# USB-TO-UART.net
KiCad netlist of a schematic drawn in Altium Designer
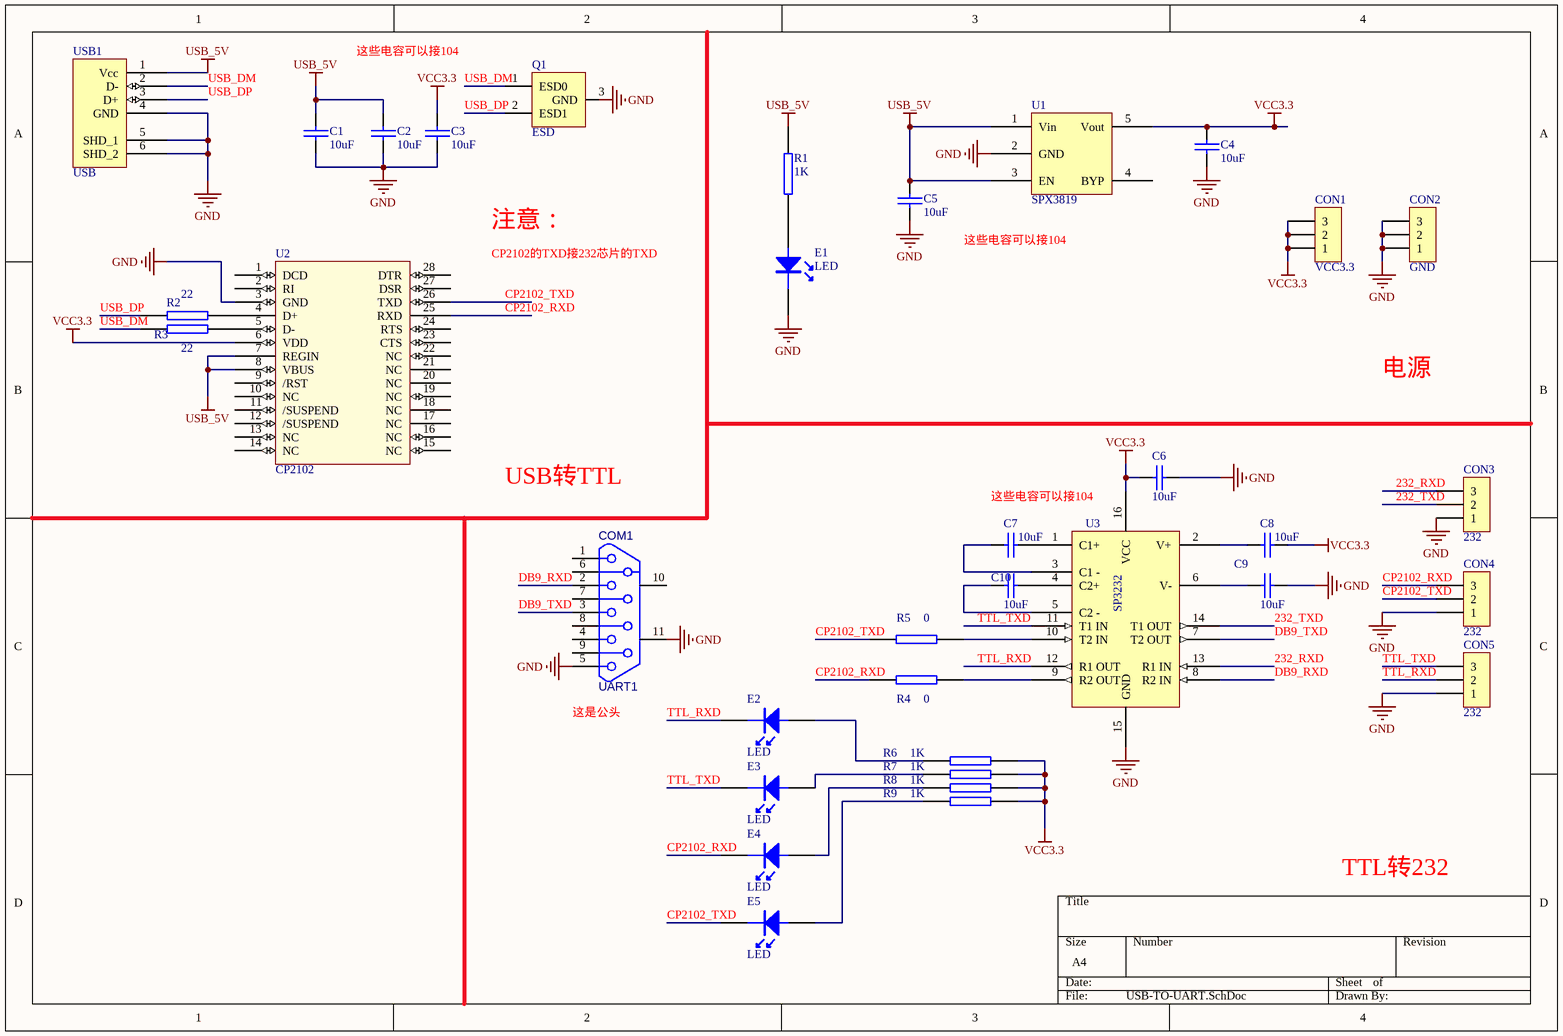
[diagram p0: USB-TO-UART.SchDoc]

(export (version "E")
  (design (tool "Eeschema 10.0.6"))
  (components
    (comp (ref "C1")
      (value "10uF")
      (footprint "0603")
      (description "无极电容")
      (libsource (lib "ZXBC") (part "CAP Nonpolarity"))
    )
    (comp (ref "C2")
      (value "10uF")
      (footprint "0603")
      (description "无极电容")
      (libsource (lib "ZXBC") (part "CAP Nonpolarity"))
    )
    (comp (ref "C3")
      (value "10uF")
      (footprint "0603")
      (description "无极电容")
      (libsource (lib "ZXBC") (part "CAP Nonpolarity"))
    )
    (comp (ref "C4")
      (value "10uF")
      (footprint "0603")
      (description "无极电容")
      (libsource (lib "ZXBC") (part "CAP Nonpolarity"))
    )
    (comp (ref "C5")
      (value "10uF")
      (footprint "0603")
      (description "无极电容")
      (libsource (lib "ZXBC") (part "CAP Nonpolarity"))
    )
    (comp (ref "C6")
      (value "10uF")
      (footprint "0603")
      (description "无极电容")
      (libsource (lib "ZXBC") (part "CAP Nonpolarity"))
    )
    (comp (ref "C7")
      (value "10uF")
      (footprint "0603")
      (description "无极电容")
      (libsource (lib "ZXBC") (part "CAP Nonpolarity"))
    )
    (comp (ref "C8")
      (value "10uF")
      (footprint "0603")
      (description "无极电容")
      (libsource (lib "ZXBC") (part "CAP Nonpolarity"))
    )
    (comp (ref "C9")
      (value "10uF")
      (footprint "0603")
      (description "无极电容")
      (libsource (lib "ZXBC") (part "CAP Nonpolarity"))
    )
    (comp (ref "C10")
      (value "10uF")
      (footprint "0603")
      (description "无极电容")
      (libsource (lib "ZXBC") (part "CAP Nonpolarity"))
    )
    (comp (ref "COM1")
      (value "UART1")
      (footprint "DB9-Male")
      (description "串口接口")
      (libsource (lib "ZXBC") (part "DB9"))
    )
    (comp (ref "CON1")
      (value "VCC3.3")
      (footprint "3 pin")
      (description "3 pin")
      (libsource (lib "ZXBC") (part "CON3"))
    )
    (comp (ref "CON2")
      (value "GND")
      (footprint "3 pin")
      (description "3 pin")
      (libsource (lib "ZXBC") (part "CON3"))
    )
    (comp (ref "CON3")
      (value "232")
      (footprint "3 pin")
      (description "3 pin")
      (libsource (lib "ZXBC") (part "CON3"))
    )
    (comp (ref "CON4")
      (value "232")
      (footprint "3 pin")
      (description "3 pin")
      (libsource (lib "ZXBC") (part "CON3"))
    )
    (comp (ref "CON5")
      (value "232")
      (footprint "3 pin")
      (description "3 pin")
      (libsource (lib "ZXBC") (part "CON3"))
    )
    (comp (ref "E1")
      (value "LED")
      (footprint "LED_0603L")
      (description "LED灯")
      (libsource (lib "ZXBC") (part "LED"))
    )
    (comp (ref "E2")
      (value "LED")
      (footprint "LED_0603L")
      (description "LED灯")
      (libsource (lib "ZXBC") (part "LED"))
    )
    (comp (ref "E3")
      (value "LED")
      (footprint "LED_0603L")
      (description "LED灯")
      (libsource (lib "ZXBC") (part "LED"))
    )
    (comp (ref "E4")
      (value "LED")
      (footprint "LED_0603L")
      (description "LED灯")
      (libsource (lib "ZXBC") (part "LED"))
    )
    (comp (ref "E5")
      (value "LED")
      (footprint "LED_0603L")
      (description "LED灯")
      (libsource (lib "ZXBC") (part "LED"))
    )
    (comp (ref "Q1")
      (value "ESD")
      (footprint "SOT32-809")
      (description "PESD1CAN")
      (libsource (lib "ZXBC") (part "ESD"))
    )
    (comp (ref "R1") (value "1K") (footprint "0603") (description "电阻") (libsource (lib "ZXBC") (part "R")))
    (comp (ref "R2") (value "22") (footprint "0603") (description "电阻") (libsource (lib "ZXBC") (part "R")))
    (comp (ref "R3") (value "22") (footprint "0603") (description "电阻") (libsource (lib "ZXBC") (part "R")))
    (comp (ref "R4") (value "0") (footprint "0603") (description "电阻") (libsource (lib "ZXBC") (part "R")))
    (comp (ref "R5") (value "0") (footprint "0603") (description "电阻") (libsource (lib "ZXBC") (part "R")))
    (comp (ref "R6") (value "1K") (footprint "0603") (description "电阻") (libsource (lib "ZXBC") (part "R")))
    (comp (ref "R7") (value "1K") (footprint "0603") (description "电阻") (libsource (lib "ZXBC") (part "R")))
    (comp (ref "R8") (value "1K") (footprint "0603") (description "电阻") (libsource (lib "ZXBC") (part "R")))
    (comp (ref "R9") (value "1K") (footprint "0603") (description "电阻") (libsource (lib "ZXBC") (part "R")))
    (comp (ref "U1")
      (value "SPX3819")
      (footprint "SOT-23-5")
      (description "稳压器")
      (libsource (lib "ZXBC") (part "SPX3819"))
    )
    (comp (ref "U2")
      (value "CP2102")
      (footprint "QFN28")
      (description "usb转usart")
      (libsource (lib "ZXBC") (part "CP2102"))
    )
    (comp (ref "U3")
      (value "SP3232")
      (footprint "SO16")
      (description "232IC")
      (libsource (lib "ZXBC") (part "SP3232"))
    )
    (comp (ref "USB1") (value "USB") (footprint "USB-TB") (libsource (lib "ZXBC") (part "USB")))
  )
  (nets
    (net (code "1") (name "/232_RXD") (class "Default")
      (node (ref "CON3") (pin "3") (pinfunction "3_3") (pintype "passive"))
      (node (ref "U3") (pin "13") (pinfunction "R1_IN_13") (pintype "input"))
    )
    (net (code "2") (name "/232_TXD") (class "Default")
      (node (ref "CON3") (pin "2") (pinfunction "2_2") (pintype "passive"))
      (node (ref "U3") (pin "14") (pinfunction "T1_OUT_14") (pintype "output"))
    )
    (net (code "3") (name "/CP2102_RXD") (class "Default")
      (node (ref "CON4") (pin "3") (pinfunction "3_3") (pintype "passive"))
      (node (ref "E4") (pin "2") (pinfunction "2_2") (pintype "passive"))
      (node (ref "R4") (pin "1") (pinfunction "1_1") (pintype "passive"))
      (node (ref "U2") (pin "25") (pinfunction "RXD_25") (pintype "power_in"))
    )
    (net (code "4") (name "/CP2102_TXD") (class "Default")
      (node (ref "CON4") (pin "2") (pinfunction "2_2") (pintype "passive"))
      (node (ref "E5") (pin "2") (pinfunction "2_2") (pintype "passive"))
      (node (ref "R5") (pin "1") (pinfunction "1_1") (pintype "passive"))
      (node (ref "U2") (pin "26") (pinfunction "TXD_26") (pintype "bidirectional"))
    )
    (net (code "5") (name "/DB9_RXD") (class "Default")
      (node (ref "COM1") (pin "2") (pinfunction "2_2") (pintype "passive"))
      (node (ref "U3") (pin "8") (pinfunction "R2_IN_8") (pintype "input"))
    )
    (net (code "6") (name "/DB9_TXD") (class "Default")
      (node (ref "COM1") (pin "3") (pinfunction "3_3") (pintype "passive"))
      (node (ref "U3") (pin "7") (pinfunction "T2_OUT_7") (pintype "output"))
    )
    (net (code "7") (name "/TTL_RXD") (class "Default")
      (node (ref "CON5") (pin "2") (pinfunction "2_2") (pintype "passive"))
      (node (ref "E2") (pin "2") (pinfunction "2_2") (pintype "passive"))
      (node (ref "U3") (pin "12") (pinfunction "R1_OUT_12") (pintype "output"))
    )
    (net (code "8") (name "/TTL_TXD") (class "Default")
      (node (ref "CON5") (pin "3") (pinfunction "3_3") (pintype "passive"))
      (node (ref "E3") (pin "2") (pinfunction "2_2") (pintype "passive"))
      (node (ref "U3") (pin "11") (pinfunction "T1_IN_11") (pintype "input"))
    )
    (net (code "9") (name "/USB_DM") (class "Default")
      (node (ref "Q1") (pin "1") (pinfunction "ESD0_1") (pintype "passive"))
      (node (ref "R3") (pin "1") (pinfunction "1_1") (pintype "passive"))
      (node (ref "USB1") (pin "2") (pinfunction "D-_2") (pintype "bidirectional"))
    )
    (net (code "10") (name "/USB_DP") (class "Default")
      (node (ref "Q1") (pin "2") (pinfunction "ESD1_2") (pintype "passive"))
      (node (ref "R2") (pin "1") (pinfunction "1_1") (pintype "passive"))
      (node (ref "USB1") (pin "3") (pinfunction "D+_3") (pintype "bidirectional"))
    )
    (net (code "11") (name "GND") (class "Default")
      (node (ref "C1") (pin "2") (pintype "passive"))
      (node (ref "C2") (pin "2") (pintype "passive"))
      (node (ref "C3") (pin "2") (pintype "passive"))
      (node (ref "C4") (pin "2") (pintype "passive"))
      (node (ref "C5") (pin "2") (pintype "passive"))
      (node (ref "C6") (pin "2") (pintype "passive"))
      (node (ref "C9") (pin "2") (pintype "passive"))
      (node (ref "COM1") (pin "11") (pinfunction "11_11") (pintype "passive"))
      (node (ref "COM1") (pin "5") (pinfunction "5_5") (pintype "passive"))
      (node (ref "CON2") (pin "1") (pinfunction "1_1") (pintype "passive"))
      (node (ref "CON2") (pin "2") (pinfunction "2_2") (pintype "passive"))
      (node (ref "CON2") (pin "3") (pinfunction "3_3") (pintype "passive"))
      (node (ref "CON3") (pin "1") (pinfunction "1_1") (pintype "passive"))
      (node (ref "CON4") (pin "1") (pinfunction "1_1") (pintype "passive"))
      (node (ref "CON5") (pin "1") (pinfunction "1_1") (pintype "passive"))
      (node (ref "E1") (pin "2") (pinfunction "2_2") (pintype "passive"))
      (node (ref "U1") (pin "2") (pinfunction "GND_2") (pintype "passive"))
      (node (ref "U2") (pin "3") (pinfunction "GND_3") (pintype "bidirectional"))
      (node (ref "U3") (pin "15") (pinfunction "GND_15") (pintype "passive"))
      (node (ref "USB1") (pin "4") (pinfunction "GND_4") (pintype "passive"))
      (node (ref "USB1") (pin "5") (pinfunction "SHD_1_5") (pintype "passive"))
      (node (ref "USB1") (pin "6") (pinfunction "SHD_2_6") (pintype "passive"))
    )
    (net (code "12") (name "Net-(E1-Pad1)") (class "Default")
      (node (ref "E1") (pin "1") (pinfunction "1_1") (pintype "passive"))
      (node (ref "R1") (pin "1") (pinfunction "1_1") (pintype "passive"))
    )
    (net (code "13") (name "Net-(E2-Pad1)") (class "Default")
      (node (ref "E2") (pin "1") (pinfunction "1_1") (pintype "passive"))
      (node (ref "R6") (pin "1") (pinfunction "1_1") (pintype "passive"))
    )
    (net (code "14") (name "Net-(E3-Pad1)") (class "Default")
      (node (ref "E3") (pin "1") (pinfunction "1_1") (pintype "passive"))
      (node (ref "R7") (pin "1") (pinfunction "1_1") (pintype "passive"))
    )
    (net (code "15") (name "Net-(E4-Pad1)") (class "Default")
      (node (ref "E4") (pin "1") (pinfunction "1_1") (pintype "passive"))
      (node (ref "R8") (pin "1") (pinfunction "1_1") (pintype "passive"))
    )
    (net (code "16") (name "Net-(E5-Pad1)") (class "Default")
      (node (ref "E5") (pin "1") (pinfunction "1_1") (pintype "passive"))
      (node (ref "R9") (pin "1") (pinfunction "1_1") (pintype "passive"))
    )
    (net (code "17") (name "Net-(U2-D+)") (class "Default")
      (node (ref "R2") (pin "2") (pinfunction "2_2") (pintype "passive"))
      (node (ref "U2") (pin "4") (pinfunction "D+_4") (pintype "power_in"))
    )
    (net (code "18") (name "Net-(U2-D-)") (class "Default")
      (node (ref "R3") (pin "2") (pinfunction "2_2") (pintype "passive"))
      (node (ref "U2") (pin "5") (pinfunction "D-_5") (pintype "bidirectional"))
    )
    (net (code "19") (name "Net-(U3-C1+)") (class "Default")
      (node (ref "C7") (pin "2") (pintype "passive"))
      (node (ref "U3") (pin "1") (pinfunction "C1+_1") (pintype "passive"))
    )
    (net (code "20") (name "Net-(U3-C1_-)") (class "Default")
      (node (ref "C7") (pin "1") (pintype "passive"))
      (node (ref "U3") (pin "3") (pinfunction "C1_-_3") (pintype "passive"))
    )
    (net (code "21") (name "Net-(U3-C2+)") (class "Default")
      (node (ref "C10") (pin "1") (pintype "passive"))
      (node (ref "U3") (pin "4") (pinfunction "C2+_4") (pintype "passive"))
    )
    (net (code "22") (name "Net-(U3-C2_-)") (class "Default")
      (node (ref "C10") (pin "2") (pintype "passive"))
      (node (ref "U3") (pin "5") (pinfunction "C2_-_5") (pintype "passive"))
    )
    (net (code "23") (name "Net-(U3-R2_OUT)") (class "Default")
      (node (ref "R4") (pin "2") (pinfunction "2_2") (pintype "passive"))
      (node (ref "U3") (pin "9") (pinfunction "R2_OUT_9") (pintype "output"))
    )
    (net (code "24") (name "Net-(U3-T2_IN)") (class "Default")
      (node (ref "R5") (pin "2") (pinfunction "2_2") (pintype "passive"))
      (node (ref "U3") (pin "10") (pinfunction "T2_IN_10") (pintype "input"))
    )
    (net (code "25") (name "Net-(U3-V+)") (class "Default")
      (node (ref "C8") (pin "1") (pintype "passive"))
      (node (ref "U3") (pin "2") (pinfunction "V+_2") (pintype "passive"))
    )
    (net (code "26") (name "Net-(U3-V-)") (class "Default")
      (node (ref "C9") (pin "1") (pintype "passive"))
      (node (ref "U3") (pin "6") (pinfunction "V-_6") (pintype "passive"))
    )
    (net (code "27") (name "USB_5V") (class "Default")
      (node (ref "C1") (pin "1") (pintype "passive"))
      (node (ref "C2") (pin "1") (pintype "passive"))
      (node (ref "C5") (pin "1") (pintype "passive"))
      (node (ref "R1") (pin "2") (pinfunction "2_2") (pintype "passive"))
      (node (ref "U1") (pin "1") (pinfunction "Vin_1") (pintype "passive"))
      (node (ref "U1") (pin "3") (pinfunction "EN_3") (pintype "passive"))
      (node (ref "U2") (pin "7") (pinfunction "REGIN_7") (pintype "power_in"))
      (node (ref "U2") (pin "8") (pinfunction "VBUS_8") (pintype "bidirectional"))
      (node (ref "USB1") (pin "1") (pinfunction "Vcc_1") (pintype "passive"))
    )
    (net (code "28") (name "VCC3.3") (class "Default")
      (node (ref "C3") (pin "1") (pintype "passive"))
      (node (ref "C4") (pin "1") (pintype "passive"))
      (node (ref "C6") (pin "1") (pintype "passive"))
      (node (ref "C8") (pin "2") (pintype "passive"))
      (node (ref "CON1") (pin "1") (pinfunction "1_1") (pintype "passive"))
      (node (ref "CON1") (pin "2") (pinfunction "2_2") (pintype "passive"))
      (node (ref "CON1") (pin "3") (pinfunction "3_3") (pintype "passive"))
      (node (ref "R6") (pin "2") (pinfunction "2_2") (pintype "passive"))
      (node (ref "R7") (pin "2") (pinfunction "2_2") (pintype "passive"))
      (node (ref "R8") (pin "2") (pinfunction "2_2") (pintype "passive"))
      (node (ref "R9") (pin "2") (pinfunction "2_2") (pintype "passive"))
      (node (ref "U1") (pin "5") (pinfunction "Vout_5") (pintype "passive"))
      (node (ref "U2") (pin "6") (pinfunction "VDD_6") (pintype "bidirectional"))
      (node (ref "U3") (pin "16") (pinfunction "VCC_16") (pintype "power_in"))
    )
    (net (code "29") (name "unconnected-(COM1-Pad1)") (class "Default")
      (node (ref "COM1") (pin "1") (pinfunction "1_1") (pintype "passive"))
    )
    (net (code "30") (name "unconnected-(COM1-Pad4)") (class "Default")
      (node (ref "COM1") (pin "4") (pinfunction "4_4") (pintype "passive"))
    )
    (net (code "31") (name "unconnected-(COM1-Pad6)") (class "Default")
      (node (ref "COM1") (pin "6") (pinfunction "6_6") (pintype "passive"))
    )
    (net (code "32") (name "unconnected-(COM1-Pad7)") (class "Default")
      (node (ref "COM1") (pin "7") (pinfunction "7_7") (pintype "passive"))
    )
    (net (code "33") (name "unconnected-(COM1-Pad8)") (class "Default")
      (node (ref "COM1") (pin "8") (pinfunction "8_8") (pintype "passive"))
    )
    (net (code "34") (name "unconnected-(COM1-Pad9)") (class "Default")
      (node (ref "COM1") (pin "9") (pinfunction "9_9") (pintype "passive"))
    )
    (net (code "35") (name "unconnected-(COM1-Pad10)") (class "Default")
      (node (ref "COM1") (pin "10") (pinfunction "10_10") (pintype "passive"))
    )
    (net (code "36") (name "unconnected-(Q1-GND-Pad3)") (class "Default")
      (node (ref "Q1") (pin "3") (pinfunction "GND_3") (pintype "passive"))
    )
    (net (code "37") (name "unconnected-(U1-BYP-Pad4)") (class "Default")
      (node (ref "U1") (pin "4") (pinfunction "BYP_4") (pintype "passive"))
    )
    (net (code "38") (name "unconnected-(U2-CTS-Pad23)") (class "Default")
      (node (ref "U2") (pin "23") (pinfunction "CTS_23") (pintype "bidirectional"))
    )
    (net (code "39") (name "unconnected-(U2-DCD-Pad1)") (class "Default")
      (node (ref "U2") (pin "1") (pinfunction "DCD_1") (pintype "bidirectional"))
    )
    (net (code "40") (name "unconnected-(U2-DSR-Pad27)") (class "Default")
      (node (ref "U2") (pin "27") (pinfunction "DSR_27") (pintype "bidirectional"))
    )
    (net (code "41") (name "unconnected-(U2-DTR-Pad28)") (class "Default")
      (node (ref "U2") (pin "28") (pinfunction "DTR_28") (pintype "bidirectional"))
    )
    (net (code "42") (name "unconnected-(U2-NC-Pad10)") (class "Default")
      (node (ref "U2") (pin "10") (pinfunction "NC_10") (pintype "bidirectional"))
    )
    (net (code "43") (name "unconnected-(U2-NC-Pad13)") (class "Default")
      (node (ref "U2") (pin "13") (pinfunction "NC_13") (pintype "bidirectional"))
    )
    (net (code "44") (name "unconnected-(U2-NC-Pad14)") (class "Default")
      (node (ref "U2") (pin "14") (pinfunction "NC_14") (pintype "bidirectional"))
    )
    (net (code "45") (name "unconnected-(U2-NC-Pad15)") (class "Default")
      (node (ref "U2") (pin "15") (pinfunction "NC_15") (pintype "bidirectional"))
    )
    (net (code "46") (name "unconnected-(U2-NC-Pad16)") (class "Default")
      (node (ref "U2") (pin "16") (pinfunction "NC_16") (pintype "bidirectional"))
    )
    (net (code "47") (name "unconnected-(U2-NC-Pad17)") (class "Default")
      (node (ref "U2") (pin "17") (pinfunction "NC_17") (pintype "power_in"))
    )
    (net (code "48") (name "unconnected-(U2-NC-Pad18)") (class "Default")
      (node (ref "U2") (pin "18") (pinfunction "NC_18") (pintype "power_in"))
    )
    (net (code "49") (name "unconnected-(U2-NC-Pad19)") (class "Default")
      (node (ref "U2") (pin "19") (pinfunction "NC_19") (pintype "bidirectional"))
    )
    (net (code "50") (name "unconnected-(U2-NC-Pad20)") (class "Default")
      (node (ref "U2") (pin "20") (pinfunction "NC_20") (pintype "power_in"))
    )
    (net (code "51") (name "unconnected-(U2-NC-Pad21)") (class "Default")
      (node (ref "U2") (pin "21") (pinfunction "NC_21") (pintype "power_in"))
    )
    (net (code "52") (name "unconnected-(U2-NC-Pad22)") (class "Default")
      (node (ref "U2") (pin "22") (pinfunction "NC_22") (pintype "bidirectional"))
    )
    (net (code "53") (name "unconnected-(U2-RI-Pad2)") (class "Default")
      (node (ref "U2") (pin "2") (pinfunction "RI_2") (pintype "bidirectional"))
    )
    (net (code "54") (name "unconnected-(U2-RTS-Pad24)") (class "Default")
      (node (ref "U2") (pin "24") (pinfunction "RTS_24") (pintype "bidirectional"))
    )
    (net (code "55") (name "unconnected-(U2-{slash}RST-Pad9)") (class "Default")
      (node (ref "U2") (pin "9") (pinfunction "/RST_9") (pintype "bidirectional"))
    )
    (net (code "56") (name "unconnected-(U2-{slash}SUSPEND-Pad11)") (class "Default")
      (node (ref "U2") (pin "11") (pinfunction "/SUSPEND_11") (pintype "bidirectional"))
    )
    (net (code "57") (name "unconnected-(U2-{slash}SUSPEND-Pad12)") (class "Default")
      (node (ref "U2") (pin "12") (pinfunction "/SUSPEND_12") (pintype "bidirectional"))
    )
  )
)
